# CAM_POWER.net
KiCad netlist of a schematic drawn in Altium Designer
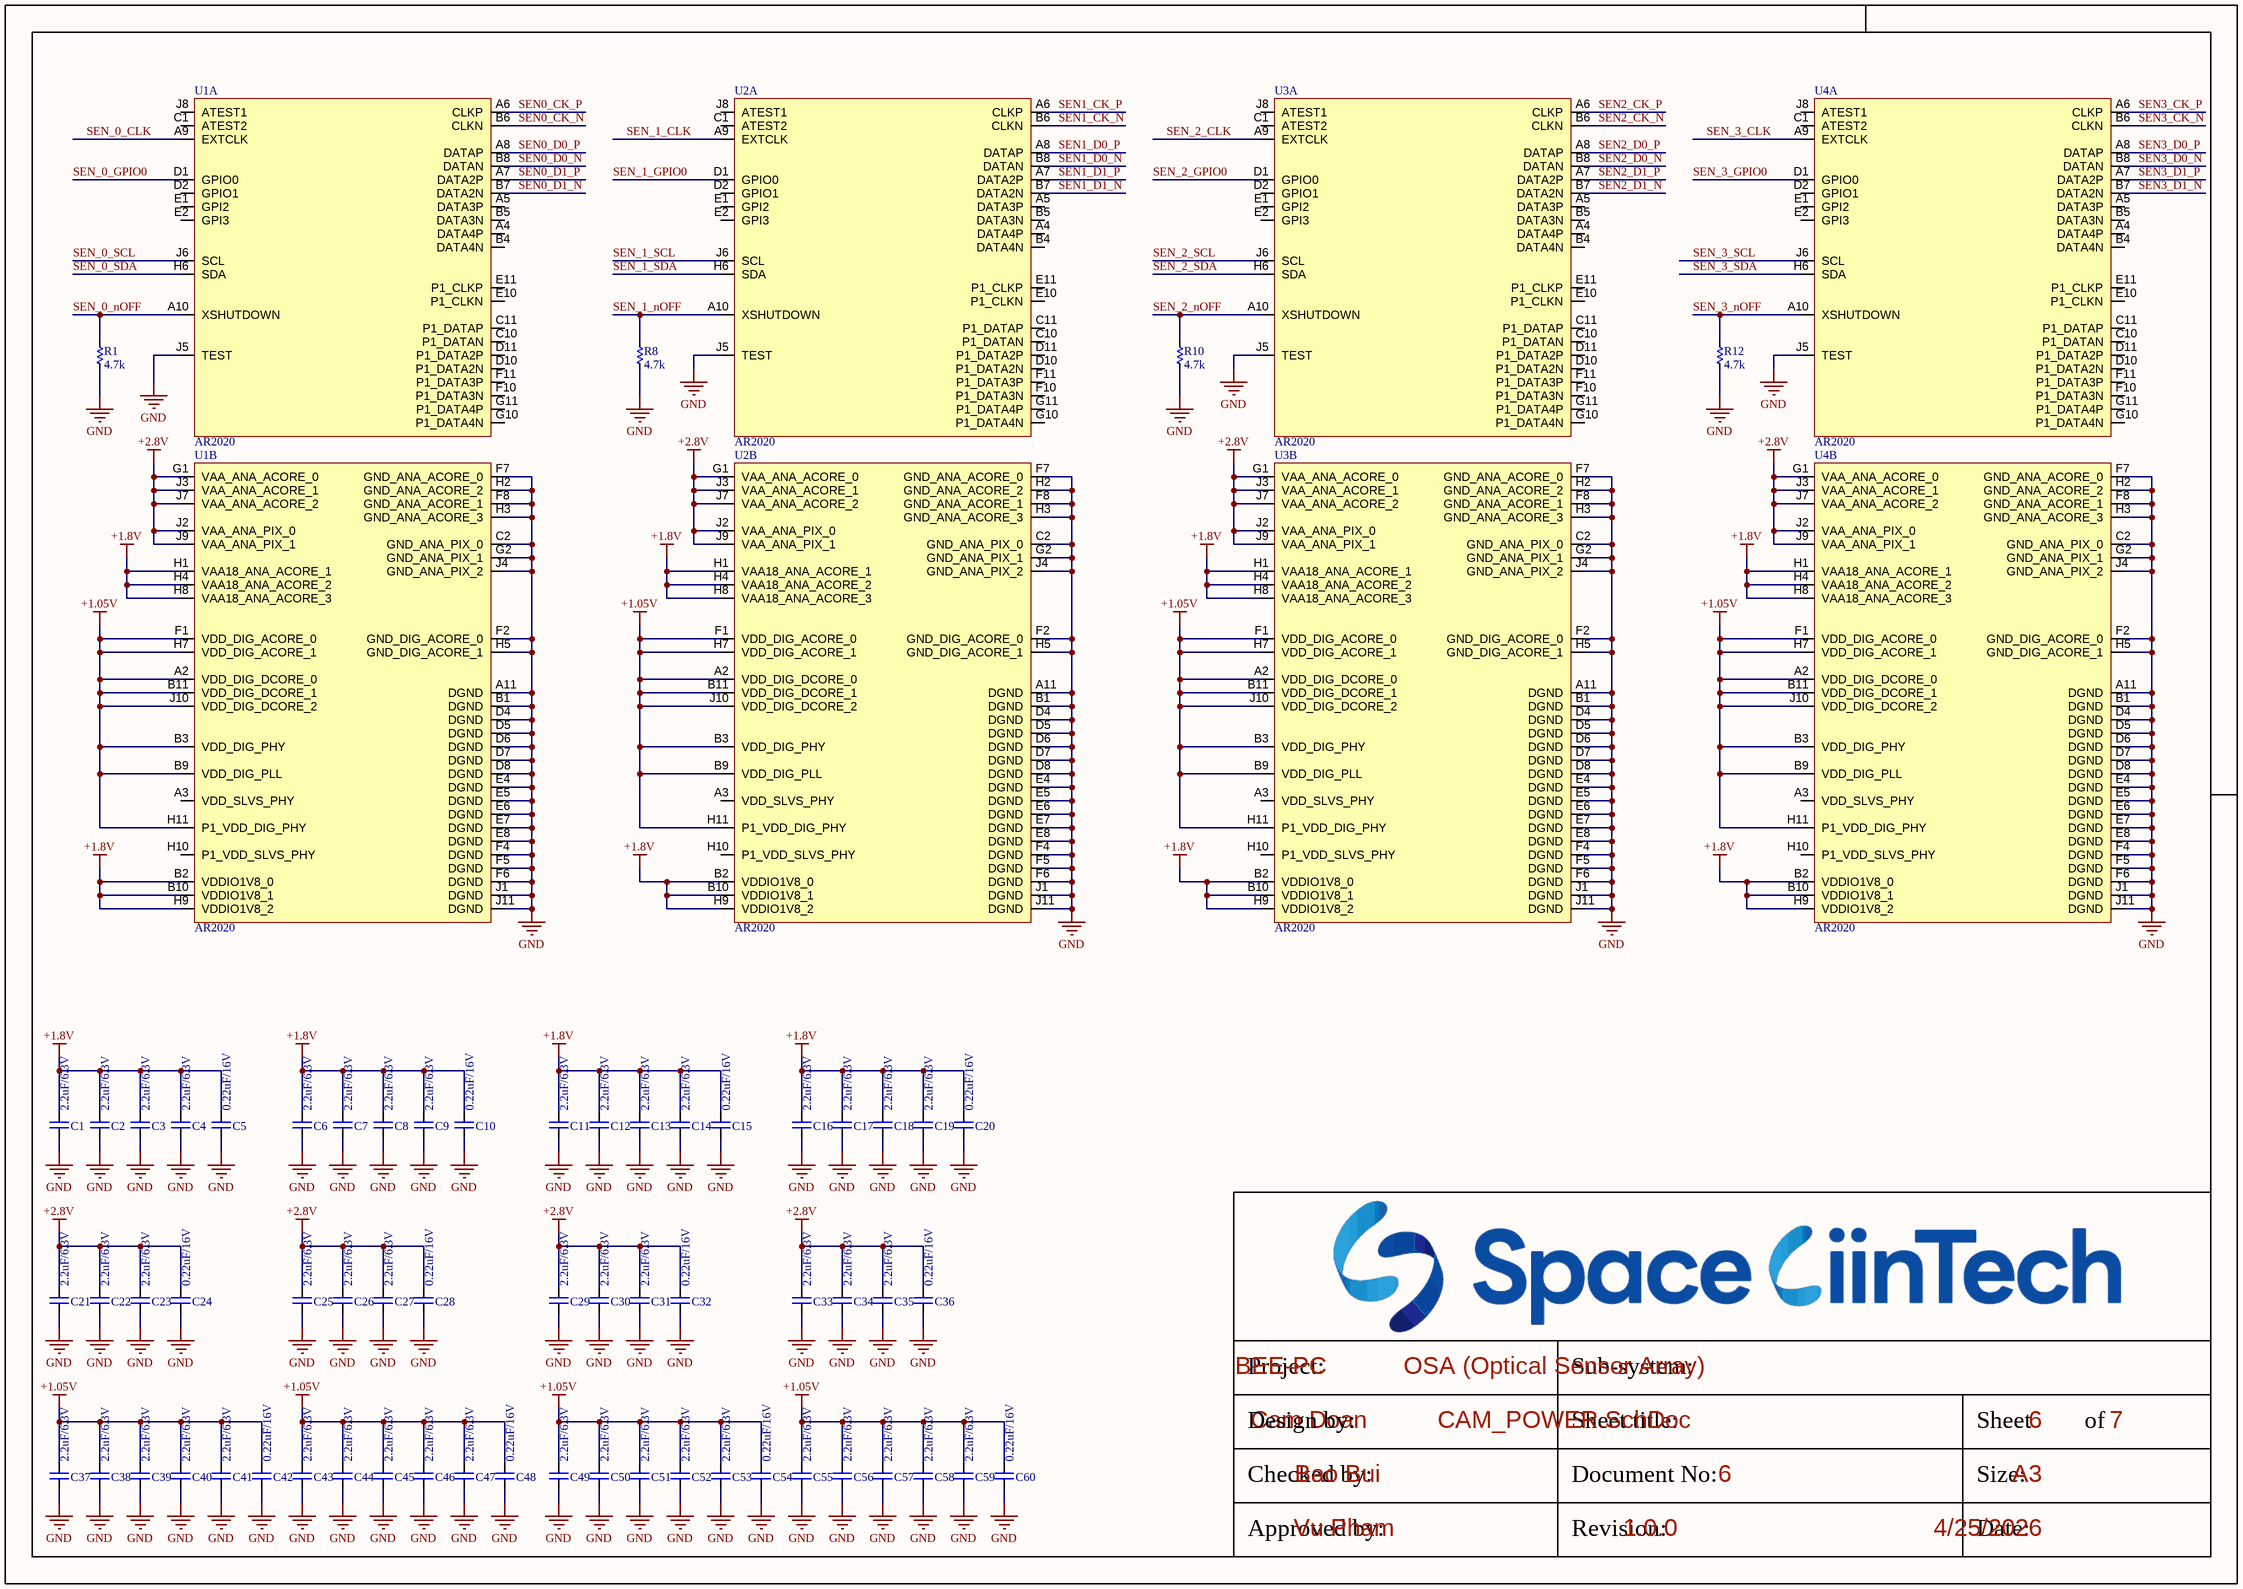
[diagram p0: CAM_POWER.SchDoc]

(export (version "E")
  (design (tool "Eeschema 10.0.6"))
  (components
    (comp (ref "C1")
      (value "2.2uF/6.3V")
      (footprint "CAP_C_1005X60")
      (description "CAP_Chip")
      (libsource (lib "LABLIB") (part "CAP_SMD"))
    )
    (comp (ref "C2")
      (value "2.2uF/6.3V")
      (footprint "CAP_C_1005X60")
      (description "CAP_Chip")
      (libsource (lib "LABLIB") (part "CAP_SMD"))
    )
    (comp (ref "C3")
      (value "2.2uF/6.3V")
      (footprint "CAP_C_1005X60")
      (description "CAP_Chip")
      (libsource (lib "LABLIB") (part "CAP_SMD"))
    )
    (comp (ref "C4")
      (value "2.2uF/6.3V")
      (footprint "CAP_C_1005X60")
      (description "CAP_Chip")
      (libsource (lib "LABLIB") (part "CAP_SMD"))
    )
    (comp (ref "C5")
      (value "0.22uF/16V")
      (footprint "CAP_C_1005X60")
      (description "CAP_Chip")
      (libsource (lib "LABLIB") (part "CAP_SMD"))
    )
    (comp (ref "C6")
      (value "2.2uF/6.3V")
      (footprint "CAP_C_1005X60")
      (description "CAP_Chip")
      (libsource (lib "LABLIB") (part "CAP_SMD"))
    )
    (comp (ref "C7")
      (value "2.2uF/6.3V")
      (footprint "CAP_C_1005X60")
      (description "CAP_Chip")
      (libsource (lib "LABLIB") (part "CAP_SMD"))
    )
    (comp (ref "C8")
      (value "2.2uF/6.3V")
      (footprint "CAP_C_1005X60")
      (description "CAP_Chip")
      (libsource (lib "LABLIB") (part "CAP_SMD"))
    )
    (comp (ref "C9")
      (value "2.2uF/6.3V")
      (footprint "CAP_C_1005X60")
      (description "CAP_Chip")
      (libsource (lib "LABLIB") (part "CAP_SMD"))
    )
    (comp (ref "C10")
      (value "0.22uF/16V")
      (footprint "CAP_C_1005X60")
      (description "CAP_Chip")
      (libsource (lib "LABLIB") (part "CAP_SMD"))
    )
    (comp (ref "C11")
      (value "2.2uF/6.3V")
      (footprint "CAP_C_1005X60")
      (description "CAP_Chip")
      (libsource (lib "LABLIB") (part "CAP_SMD"))
    )
    (comp (ref "C12")
      (value "2.2uF/6.3V")
      (footprint "CAP_C_1005X60")
      (description "CAP_Chip")
      (libsource (lib "LABLIB") (part "CAP_SMD"))
    )
    (comp (ref "C13")
      (value "2.2uF/6.3V")
      (footprint "CAP_C_1005X60")
      (description "CAP_Chip")
      (libsource (lib "LABLIB") (part "CAP_SMD"))
    )
    (comp (ref "C14")
      (value "2.2uF/6.3V")
      (footprint "CAP_C_1005X60")
      (description "CAP_Chip")
      (libsource (lib "LABLIB") (part "CAP_SMD"))
    )
    (comp (ref "C15")
      (value "0.22uF/16V")
      (footprint "CAP_C_1005X60")
      (description "CAP_Chip")
      (libsource (lib "LABLIB") (part "CAP_SMD"))
    )
    (comp (ref "C16")
      (value "2.2uF/6.3V")
      (footprint "CAP_C_1005X60")
      (description "CAP_Chip")
      (libsource (lib "LABLIB") (part "CAP_SMD"))
    )
    (comp (ref "C17")
      (value "2.2uF/6.3V")
      (footprint "CAP_C_1005X60")
      (description "CAP_Chip")
      (libsource (lib "LABLIB") (part "CAP_SMD"))
    )
    (comp (ref "C18")
      (value "2.2uF/6.3V")
      (footprint "CAP_C_1005X60")
      (description "CAP_Chip")
      (libsource (lib "LABLIB") (part "CAP_SMD"))
    )
    (comp (ref "C19")
      (value "2.2uF/6.3V")
      (footprint "CAP_C_1005X60")
      (description "CAP_Chip")
      (libsource (lib "LABLIB") (part "CAP_SMD"))
    )
    (comp (ref "C20")
      (value "0.22uF/16V")
      (footprint "CAP_C_1005X60")
      (description "CAP_Chip")
      (libsource (lib "LABLIB") (part "CAP_SMD"))
    )
    (comp (ref "C21")
      (value "2.2uF/6.3V")
      (footprint "CAP_C_1005X60")
      (description "CAP_Chip")
      (libsource (lib "LABLIB") (part "CAP_SMD"))
    )
    (comp (ref "C22")
      (value "2.2uF/6.3V")
      (footprint "CAP_C_1005X60")
      (description "CAP_Chip")
      (libsource (lib "LABLIB") (part "CAP_SMD"))
    )
    (comp (ref "C23")
      (value "2.2uF/6.3V")
      (footprint "CAP_C_1005X60")
      (description "CAP_Chip")
      (libsource (lib "LABLIB") (part "CAP_SMD"))
    )
    (comp (ref "C24")
      (value "0.22uF/16V")
      (footprint "CAP_C_1005X60")
      (description "CAP_Chip")
      (libsource (lib "LABLIB") (part "CAP_SMD"))
    )
    (comp (ref "C25")
      (value "2.2uF/6.3V")
      (footprint "CAP_C_1005X60")
      (description "CAP_Chip")
      (libsource (lib "LABLIB") (part "CAP_SMD"))
    )
    (comp (ref "C26")
      (value "2.2uF/6.3V")
      (footprint "CAP_C_1005X60")
      (description "CAP_Chip")
      (libsource (lib "LABLIB") (part "CAP_SMD"))
    )
    (comp (ref "C27")
      (value "2.2uF/6.3V")
      (footprint "CAP_C_1005X60")
      (description "CAP_Chip")
      (libsource (lib "LABLIB") (part "CAP_SMD"))
    )
    (comp (ref "C28")
      (value "0.22uF/16V")
      (footprint "CAP_C_1005X60")
      (description "CAP_Chip")
      (libsource (lib "LABLIB") (part "CAP_SMD"))
    )
    (comp (ref "C29")
      (value "2.2uF/6.3V")
      (footprint "CAP_C_1005X60")
      (description "CAP_Chip")
      (libsource (lib "LABLIB") (part "CAP_SMD"))
    )
    (comp (ref "C30")
      (value "2.2uF/6.3V")
      (footprint "CAP_C_1005X60")
      (description "CAP_Chip")
      (libsource (lib "LABLIB") (part "CAP_SMD"))
    )
    (comp (ref "C31")
      (value "2.2uF/6.3V")
      (footprint "CAP_C_1005X60")
      (description "CAP_Chip")
      (libsource (lib "LABLIB") (part "CAP_SMD"))
    )
    (comp (ref "C32")
      (value "0.22uF/16V")
      (footprint "CAP_C_1005X60")
      (description "CAP_Chip")
      (libsource (lib "LABLIB") (part "CAP_SMD"))
    )
    (comp (ref "C33")
      (value "2.2uF/6.3V")
      (footprint "CAP_C_1005X60")
      (description "CAP_Chip")
      (libsource (lib "LABLIB") (part "CAP_SMD"))
    )
    (comp (ref "C34")
      (value "2.2uF/6.3V")
      (footprint "CAP_C_1005X60")
      (description "CAP_Chip")
      (libsource (lib "LABLIB") (part "CAP_SMD"))
    )
    (comp (ref "C35")
      (value "2.2uF/6.3V")
      (footprint "CAP_C_1005X60")
      (description "CAP_Chip")
      (libsource (lib "LABLIB") (part "CAP_SMD"))
    )
    (comp (ref "C36")
      (value "0.22uF/16V")
      (footprint "CAP_C_1005X60")
      (description "CAP_Chip")
      (libsource (lib "LABLIB") (part "CAP_SMD"))
    )
    (comp (ref "C37")
      (value "2.2uF/6.3V")
      (footprint "CAP_C_1005X60")
      (description "CAP_Chip")
      (libsource (lib "LABLIB") (part "CAP_SMD"))
    )
    (comp (ref "C38")
      (value "2.2uF/6.3V")
      (footprint "CAP_C_1005X60")
      (description "CAP_Chip")
      (libsource (lib "LABLIB") (part "CAP_SMD"))
    )
    (comp (ref "C39")
      (value "2.2uF/6.3V")
      (footprint "CAP_C_1005X60")
      (description "CAP_Chip")
      (libsource (lib "LABLIB") (part "CAP_SMD"))
    )
    (comp (ref "C40")
      (value "2.2uF/6.3V")
      (footprint "CAP_C_1005X60")
      (description "CAP_Chip")
      (libsource (lib "LABLIB") (part "CAP_SMD"))
    )
    (comp (ref "C41")
      (value "2.2uF/6.3V")
      (footprint "CAP_C_1005X60")
      (description "CAP_Chip")
      (libsource (lib "LABLIB") (part "CAP_SMD"))
    )
    (comp (ref "C42")
      (value "0.22uF/16V")
      (footprint "CAP_C_1005X60")
      (description "CAP_Chip")
      (libsource (lib "LABLIB") (part "CAP_SMD"))
    )
    (comp (ref "C43")
      (value "2.2uF/6.3V")
      (footprint "CAP_C_1005X60")
      (description "CAP_Chip")
      (libsource (lib "LABLIB") (part "CAP_SMD"))
    )
    (comp (ref "C44")
      (value "2.2uF/6.3V")
      (footprint "CAP_C_1005X60")
      (description "CAP_Chip")
      (libsource (lib "LABLIB") (part "CAP_SMD"))
    )
    (comp (ref "C45")
      (value "2.2uF/6.3V")
      (footprint "CAP_C_1005X60")
      (description "CAP_Chip")
      (libsource (lib "LABLIB") (part "CAP_SMD"))
    )
    (comp (ref "C46")
      (value "2.2uF/6.3V")
      (footprint "CAP_C_1005X60")
      (description "CAP_Chip")
      (libsource (lib "LABLIB") (part "CAP_SMD"))
    )
    (comp (ref "C47")
      (value "2.2uF/6.3V")
      (footprint "CAP_C_1005X60")
      (description "CAP_Chip")
      (libsource (lib "LABLIB") (part "CAP_SMD"))
    )
    (comp (ref "C48")
      (value "0.22uF/16V")
      (footprint "CAP_C_1005X60")
      (description "CAP_Chip")
      (libsource (lib "LABLIB") (part "CAP_SMD"))
    )
    (comp (ref "C49")
      (value "2.2uF/6.3V")
      (footprint "CAP_C_1005X60")
      (description "CAP_Chip")
      (libsource (lib "LABLIB") (part "CAP_SMD"))
    )
    (comp (ref "C50")
      (value "2.2uF/6.3V")
      (footprint "CAP_C_1005X60")
      (description "CAP_Chip")
      (libsource (lib "LABLIB") (part "CAP_SMD"))
    )
    (comp (ref "C51")
      (value "2.2uF/6.3V")
      (footprint "CAP_C_1005X60")
      (description "CAP_Chip")
      (libsource (lib "LABLIB") (part "CAP_SMD"))
    )
    (comp (ref "C52")
      (value "2.2uF/6.3V")
      (footprint "CAP_C_1005X60")
      (description "CAP_Chip")
      (libsource (lib "LABLIB") (part "CAP_SMD"))
    )
    (comp (ref "C53")
      (value "2.2uF/6.3V")
      (footprint "CAP_C_1005X60")
      (description "CAP_Chip")
      (libsource (lib "LABLIB") (part "CAP_SMD"))
    )
    (comp (ref "C54")
      (value "0.22uF/16V")
      (footprint "CAP_C_1005X60")
      (description "CAP_Chip")
      (libsource (lib "LABLIB") (part "CAP_SMD"))
    )
    (comp (ref "C55")
      (value "2.2uF/6.3V")
      (footprint "CAP_C_1005X60")
      (description "CAP_Chip")
      (libsource (lib "LABLIB") (part "CAP_SMD"))
    )
    (comp (ref "C56")
      (value "2.2uF/6.3V")
      (footprint "CAP_C_1005X60")
      (description "CAP_Chip")
      (libsource (lib "LABLIB") (part "CAP_SMD"))
    )
    (comp (ref "C57")
      (value "2.2uF/6.3V")
      (footprint "CAP_C_1005X60")
      (description "CAP_Chip")
      (libsource (lib "LABLIB") (part "CAP_SMD"))
    )
    (comp (ref "C58")
      (value "2.2uF/6.3V")
      (footprint "CAP_C_1005X60")
      (description "CAP_Chip")
      (libsource (lib "LABLIB") (part "CAP_SMD"))
    )
    (comp (ref "C59")
      (value "2.2uF/6.3V")
      (footprint "CAP_C_1005X60")
      (description "CAP_Chip")
      (libsource (lib "LABLIB") (part "CAP_SMD"))
    )
    (comp (ref "C60")
      (value "0.22uF/16V")
      (footprint "CAP_C_1005X60")
      (description "CAP_Chip")
      (libsource (lib "LABLIB") (part "CAP_SMD"))
    )
    (comp (ref "R1")
      (value "4.7k")
      (footprint "RES_C_1005X40")
      (description "RES-Chip")
      (fields
        (field (name "MANUFACTURER") "Generic Components")
        (field (name "PUBLISHER") "Altium Hobart Technology Centre")
      )
      (libsource (lib "LABLIB") (part "RES-SMD"))
    )
    (comp (ref "R8")
      (value "4.7k")
      (footprint "RES_C_1005X40")
      (description "RES-Chip")
      (fields
        (field (name "MANUFACTURER") "Generic Components")
        (field (name "PUBLISHER") "Altium Hobart Technology Centre")
      )
      (libsource (lib "LABLIB") (part "RES-SMD"))
    )
    (comp (ref "R10")
      (value "4.7k")
      (footprint "RES_C_1005X40")
      (description "RES-Chip")
      (fields
        (field (name "MANUFACTURER") "Generic Components")
        (field (name "PUBLISHER") "Altium Hobart Technology Centre")
      )
      (libsource (lib "LABLIB") (part "RES-SMD"))
    )
    (comp (ref "R12")
      (value "4.7k")
      (footprint "RES_C_1005X40")
      (description "RES-Chip")
      (fields
        (field (name "MANUFACTURER") "Generic Components")
        (field (name "PUBLISHER") "Altium Hobart Technology Centre")
      )
      (libsource (lib "LABLIB") (part "RES-SMD"))
    )
    (comp (ref "U1")
      (value "AR2020")
      (footprint "BGA78C100P11X9_1300X1050X210")
      (libsource (lib "CAMERA_SchLib") (part "AR2020"))
    )
    (comp (ref "U2")
      (value "AR2020")
      (footprint "BGA78C100P11X9_1300X1050X210")
      (libsource (lib "CAMERA_SchLib") (part "AR2020"))
    )
    (comp (ref "U3")
      (value "AR2020")
      (footprint "BGA78C100P11X9_1300X1050X210")
      (libsource (lib "CAMERA_SchLib") (part "AR2020"))
    )
    (comp (ref "U4")
      (value "AR2020")
      (footprint "BGA78C100P11X9_1300X1050X210")
      (libsource (lib "CAMERA_SchLib") (part "AR2020"))
    )
  )
  (nets
    (net (code "1") (name "+1.05V") (class "Default")
      (node (ref "C37") (pin "2") (pinfunction "2_2") (pintype "passive"))
      (node (ref "C38") (pin "2") (pinfunction "2_2") (pintype "passive"))
      (node (ref "C39") (pin "2") (pinfunction "2_2") (pintype "passive"))
      (node (ref "C40") (pin "2") (pinfunction "2_2") (pintype "passive"))
      (node (ref "C41") (pin "2") (pinfunction "2_2") (pintype "passive"))
      (node (ref "C42") (pin "2") (pinfunction "2_2") (pintype "passive"))
      (node (ref "C43") (pin "2") (pinfunction "2_2") (pintype "passive"))
      (node (ref "C44") (pin "2") (pinfunction "2_2") (pintype "passive"))
      (node (ref "C45") (pin "2") (pinfunction "2_2") (pintype "passive"))
      (node (ref "C46") (pin "2") (pinfunction "2_2") (pintype "passive"))
      (node (ref "C47") (pin "2") (pinfunction "2_2") (pintype "passive"))
      (node (ref "C48") (pin "2") (pinfunction "2_2") (pintype "passive"))
      (node (ref "C49") (pin "2") (pinfunction "2_2") (pintype "passive"))
      (node (ref "C50") (pin "2") (pinfunction "2_2") (pintype "passive"))
      (node (ref "C51") (pin "2") (pinfunction "2_2") (pintype "passive"))
      (node (ref "C52") (pin "2") (pinfunction "2_2") (pintype "passive"))
      (node (ref "C53") (pin "2") (pinfunction "2_2") (pintype "passive"))
      (node (ref "C54") (pin "2") (pinfunction "2_2") (pintype "passive"))
      (node (ref "C55") (pin "2") (pinfunction "2_2") (pintype "passive"))
      (node (ref "C56") (pin "2") (pinfunction "2_2") (pintype "passive"))
      (node (ref "C57") (pin "2") (pinfunction "2_2") (pintype "passive"))
      (node (ref "C58") (pin "2") (pinfunction "2_2") (pintype "passive"))
      (node (ref "C59") (pin "2") (pinfunction "2_2") (pintype "passive"))
      (node (ref "C60") (pin "2") (pinfunction "2_2") (pintype "passive"))
      (node (ref "U1") (pin "A2") (pinfunction "VDD_DIG_DCORE_0_A2") (pintype "passive"))
      (node (ref "U1") (pin "B11") (pinfunction "VDD_DIG_DCORE_1_B11") (pintype "passive"))
      (node (ref "U1") (pin "B3") (pinfunction "VDD_DIG_PHY_B3") (pintype "passive"))
      (node (ref "U1") (pin "B9") (pinfunction "VDD_DIG_PLL_B9") (pintype "passive"))
      (node (ref "U1") (pin "F1") (pinfunction "VDD_DIG_ACORE_0_F1") (pintype "passive"))
      (node (ref "U1") (pin "H11") (pinfunction "P1_VDD_DIG_PHY_H11") (pintype "passive"))
      (node (ref "U1") (pin "H7") (pinfunction "VDD_DIG_ACORE_1_H7") (pintype "passive"))
      (node (ref "U1") (pin "J10") (pinfunction "VDD_DIG_DCORE_2_J10") (pintype "passive"))
      (node (ref "U2") (pin "A2") (pinfunction "VDD_DIG_DCORE_0_A2") (pintype "passive"))
      (node (ref "U2") (pin "B11") (pinfunction "VDD_DIG_DCORE_1_B11") (pintype "passive"))
      (node (ref "U2") (pin "B3") (pinfunction "VDD_DIG_PHY_B3") (pintype "passive"))
      (node (ref "U2") (pin "B9") (pinfunction "VDD_DIG_PLL_B9") (pintype "passive"))
      (node (ref "U2") (pin "F1") (pinfunction "VDD_DIG_ACORE_0_F1") (pintype "passive"))
      (node (ref "U2") (pin "H11") (pinfunction "P1_VDD_DIG_PHY_H11") (pintype "passive"))
      (node (ref "U2") (pin "H7") (pinfunction "VDD_DIG_ACORE_1_H7") (pintype "passive"))
      (node (ref "U2") (pin "J10") (pinfunction "VDD_DIG_DCORE_2_J10") (pintype "passive"))
      (node (ref "U3") (pin "A2") (pinfunction "VDD_DIG_DCORE_0_A2") (pintype "passive"))
      (node (ref "U3") (pin "B11") (pinfunction "VDD_DIG_DCORE_1_B11") (pintype "passive"))
      (node (ref "U3") (pin "B3") (pinfunction "VDD_DIG_PHY_B3") (pintype "passive"))
      (node (ref "U3") (pin "B9") (pinfunction "VDD_DIG_PLL_B9") (pintype "passive"))
      (node (ref "U3") (pin "F1") (pinfunction "VDD_DIG_ACORE_0_F1") (pintype "passive"))
      (node (ref "U3") (pin "H11") (pinfunction "P1_VDD_DIG_PHY_H11") (pintype "passive"))
      (node (ref "U3") (pin "H7") (pinfunction "VDD_DIG_ACORE_1_H7") (pintype "passive"))
      (node (ref "U3") (pin "J10") (pinfunction "VDD_DIG_DCORE_2_J10") (pintype "passive"))
      (node (ref "U4") (pin "A2") (pinfunction "VDD_DIG_DCORE_0_A2") (pintype "passive"))
      (node (ref "U4") (pin "B11") (pinfunction "VDD_DIG_DCORE_1_B11") (pintype "passive"))
      (node (ref "U4") (pin "B3") (pinfunction "VDD_DIG_PHY_B3") (pintype "passive"))
      (node (ref "U4") (pin "B9") (pinfunction "VDD_DIG_PLL_B9") (pintype "passive"))
      (node (ref "U4") (pin "F1") (pinfunction "VDD_DIG_ACORE_0_F1") (pintype "passive"))
      (node (ref "U4") (pin "H11") (pinfunction "P1_VDD_DIG_PHY_H11") (pintype "passive"))
      (node (ref "U4") (pin "H7") (pinfunction "VDD_DIG_ACORE_1_H7") (pintype "passive"))
      (node (ref "U4") (pin "J10") (pinfunction "VDD_DIG_DCORE_2_J10") (pintype "passive"))
    )
    (net (code "2") (name "+1.8V") (class "Default")
      (node (ref "C1") (pin "2") (pinfunction "2_2") (pintype "passive"))
      (node (ref "C10") (pin "2") (pinfunction "2_2") (pintype "passive"))
      (node (ref "C11") (pin "2") (pinfunction "2_2") (pintype "passive"))
      (node (ref "C12") (pin "2") (pinfunction "2_2") (pintype "passive"))
      (node (ref "C13") (pin "2") (pinfunction "2_2") (pintype "passive"))
      (node (ref "C14") (pin "2") (pinfunction "2_2") (pintype "passive"))
      (node (ref "C15") (pin "2") (pinfunction "2_2") (pintype "passive"))
      (node (ref "C16") (pin "2") (pinfunction "2_2") (pintype "passive"))
      (node (ref "C17") (pin "2") (pinfunction "2_2") (pintype "passive"))
      (node (ref "C18") (pin "2") (pinfunction "2_2") (pintype "passive"))
      (node (ref "C19") (pin "2") (pinfunction "2_2") (pintype "passive"))
      (node (ref "C2") (pin "2") (pinfunction "2_2") (pintype "passive"))
      (node (ref "C20") (pin "2") (pinfunction "2_2") (pintype "passive"))
      (node (ref "C3") (pin "2") (pinfunction "2_2") (pintype "passive"))
      (node (ref "C4") (pin "2") (pinfunction "2_2") (pintype "passive"))
      (node (ref "C5") (pin "2") (pinfunction "2_2") (pintype "passive"))
      (node (ref "C6") (pin "2") (pinfunction "2_2") (pintype "passive"))
      (node (ref "C7") (pin "2") (pinfunction "2_2") (pintype "passive"))
      (node (ref "C8") (pin "2") (pinfunction "2_2") (pintype "passive"))
      (node (ref "C9") (pin "2") (pinfunction "2_2") (pintype "passive"))
      (node (ref "U1") (pin "B10") (pinfunction "VDDIO1V8_1_B10") (pintype "passive"))
      (node (ref "U1") (pin "B2") (pinfunction "VDDIO1V8_0_B2") (pintype "passive"))
      (node (ref "U1") (pin "H1") (pinfunction "VAA18_ANA_ACORE_1_H1") (pintype "passive"))
      (node (ref "U1") (pin "H4") (pinfunction "VAA18_ANA_ACORE_2_H4") (pintype "passive"))
      (node (ref "U1") (pin "H8") (pinfunction "VAA18_ANA_ACORE_3_H8") (pintype "passive"))
      (node (ref "U1") (pin "H9") (pinfunction "VDDIO1V8_2_H9") (pintype "passive"))
      (node (ref "U2") (pin "B10") (pinfunction "VDDIO1V8_1_B10") (pintype "passive"))
      (node (ref "U2") (pin "B2") (pinfunction "VDDIO1V8_0_B2") (pintype "passive"))
      (node (ref "U2") (pin "H1") (pinfunction "VAA18_ANA_ACORE_1_H1") (pintype "passive"))
      (node (ref "U2") (pin "H4") (pinfunction "VAA18_ANA_ACORE_2_H4") (pintype "passive"))
      (node (ref "U2") (pin "H8") (pinfunction "VAA18_ANA_ACORE_3_H8") (pintype "passive"))
      (node (ref "U2") (pin "H9") (pinfunction "VDDIO1V8_2_H9") (pintype "passive"))
      (node (ref "U3") (pin "B10") (pinfunction "VDDIO1V8_1_B10") (pintype "passive"))
      (node (ref "U3") (pin "B2") (pinfunction "VDDIO1V8_0_B2") (pintype "passive"))
      (node (ref "U3") (pin "H1") (pinfunction "VAA18_ANA_ACORE_1_H1") (pintype "passive"))
      (node (ref "U3") (pin "H4") (pinfunction "VAA18_ANA_ACORE_2_H4") (pintype "passive"))
      (node (ref "U3") (pin "H8") (pinfunction "VAA18_ANA_ACORE_3_H8") (pintype "passive"))
      (node (ref "U3") (pin "H9") (pinfunction "VDDIO1V8_2_H9") (pintype "passive"))
      (node (ref "U4") (pin "B10") (pinfunction "VDDIO1V8_1_B10") (pintype "passive"))
      (node (ref "U4") (pin "B2") (pinfunction "VDDIO1V8_0_B2") (pintype "passive"))
      (node (ref "U4") (pin "H1") (pinfunction "VAA18_ANA_ACORE_1_H1") (pintype "passive"))
      (node (ref "U4") (pin "H4") (pinfunction "VAA18_ANA_ACORE_2_H4") (pintype "passive"))
      (node (ref "U4") (pin "H8") (pinfunction "VAA18_ANA_ACORE_3_H8") (pintype "passive"))
      (node (ref "U4") (pin "H9") (pinfunction "VDDIO1V8_2_H9") (pintype "passive"))
    )
    (net (code "3") (name "+2.8V") (class "Default")
      (node (ref "C21") (pin "2") (pinfunction "2_2") (pintype "passive"))
      (node (ref "C22") (pin "2") (pinfunction "2_2") (pintype "passive"))
      (node (ref "C23") (pin "2") (pinfunction "2_2") (pintype "passive"))
      (node (ref "C24") (pin "2") (pinfunction "2_2") (pintype "passive"))
      (node (ref "C25") (pin "2") (pinfunction "2_2") (pintype "passive"))
      (node (ref "C26") (pin "2") (pinfunction "2_2") (pintype "passive"))
      (node (ref "C27") (pin "2") (pinfunction "2_2") (pintype "passive"))
      (node (ref "C28") (pin "2") (pinfunction "2_2") (pintype "passive"))
      (node (ref "C29") (pin "2") (pinfunction "2_2") (pintype "passive"))
      (node (ref "C30") (pin "2") (pinfunction "2_2") (pintype "passive"))
      (node (ref "C31") (pin "2") (pinfunction "2_2") (pintype "passive"))
      (node (ref "C32") (pin "2") (pinfunction "2_2") (pintype "passive"))
      (node (ref "C33") (pin "2") (pinfunction "2_2") (pintype "passive"))
      (node (ref "C34") (pin "2") (pinfunction "2_2") (pintype "passive"))
      (node (ref "C35") (pin "2") (pinfunction "2_2") (pintype "passive"))
      (node (ref "C36") (pin "2") (pinfunction "2_2") (pintype "passive"))
      (node (ref "U1") (pin "G1") (pinfunction "VAA_ANA_ACORE_0_G1") (pintype "passive"))
      (node (ref "U1") (pin "J2") (pinfunction "VAA_ANA_PIX_0_J2") (pintype "passive"))
      (node (ref "U1") (pin "J3") (pinfunction "VAA_ANA_ACORE_1_J3") (pintype "passive"))
      (node (ref "U1") (pin "J7") (pinfunction "VAA_ANA_ACORE_2_J7") (pintype "passive"))
      (node (ref "U1") (pin "J9") (pinfunction "VAA_ANA_PIX_1_J9") (pintype "passive"))
      (node (ref "U2") (pin "G1") (pinfunction "VAA_ANA_ACORE_0_G1") (pintype "passive"))
      (node (ref "U2") (pin "J2") (pinfunction "VAA_ANA_PIX_0_J2") (pintype "passive"))
      (node (ref "U2") (pin "J3") (pinfunction "VAA_ANA_ACORE_1_J3") (pintype "passive"))
      (node (ref "U2") (pin "J7") (pinfunction "VAA_ANA_ACORE_2_J7") (pintype "passive"))
      (node (ref "U2") (pin "J9") (pinfunction "VAA_ANA_PIX_1_J9") (pintype "passive"))
      (node (ref "U3") (pin "G1") (pinfunction "VAA_ANA_ACORE_0_G1") (pintype "passive"))
      (node (ref "U3") (pin "J2") (pinfunction "VAA_ANA_PIX_0_J2") (pintype "passive"))
      (node (ref "U3") (pin "J3") (pinfunction "VAA_ANA_ACORE_1_J3") (pintype "passive"))
      (node (ref "U3") (pin "J7") (pinfunction "VAA_ANA_ACORE_2_J7") (pintype "passive"))
      (node (ref "U3") (pin "J9") (pinfunction "VAA_ANA_PIX_1_J9") (pintype "passive"))
      (node (ref "U4") (pin "G1") (pinfunction "VAA_ANA_ACORE_0_G1") (pintype "passive"))
      (node (ref "U4") (pin "J2") (pinfunction "VAA_ANA_PIX_0_J2") (pintype "passive"))
      (node (ref "U4") (pin "J3") (pinfunction "VAA_ANA_ACORE_1_J3") (pintype "passive"))
      (node (ref "U4") (pin "J7") (pinfunction "VAA_ANA_ACORE_2_J7") (pintype "passive"))
      (node (ref "U4") (pin "J9") (pinfunction "VAA_ANA_PIX_1_J9") (pintype "passive"))
    )
    (net (code "4") (name "/SEN0_CK_N") (class "Default")
      (node (ref "U1") (pin "B6") (pinfunction "CLKN_B6") (pintype "passive"))
    )
    (net (code "5") (name "/SEN0_CK_P") (class "Default")
      (node (ref "U1") (pin "A6") (pinfunction "CLKP_A6") (pintype "passive"))
    )
    (net (code "6") (name "/SEN0_D0_N") (class "Default")
      (node (ref "U1") (pin "B8") (pinfunction "DATAN_B8") (pintype "passive"))
    )
    (net (code "7") (name "/SEN0_D0_P") (class "Default")
      (node (ref "U1") (pin "A8") (pinfunction "DATAP_A8") (pintype "passive"))
    )
    (net (code "8") (name "/SEN0_D1_N") (class "Default")
      (node (ref "U1") (pin "B7") (pinfunction "DATA2N_B7") (pintype "passive"))
    )
    (net (code "9") (name "/SEN0_D1_P") (class "Default")
      (node (ref "U1") (pin "A7") (pinfunction "DATA2P_A7") (pintype "passive"))
    )
    (net (code "10") (name "/SEN1_CK_N") (class "Default")
      (node (ref "U2") (pin "B6") (pinfunction "CLKN_B6") (pintype "passive"))
    )
    (net (code "11") (name "/SEN1_CK_P") (class "Default")
      (node (ref "U2") (pin "A6") (pinfunction "CLKP_A6") (pintype "passive"))
    )
    (net (code "12") (name "/SEN1_D0_N") (class "Default")
      (node (ref "U2") (pin "B8") (pinfunction "DATAN_B8") (pintype "passive"))
    )
    (net (code "13") (name "/SEN1_D0_P") (class "Default")
      (node (ref "U2") (pin "A8") (pinfunction "DATAP_A8") (pintype "passive"))
    )
    (net (code "14") (name "/SEN1_D1_N") (class "Default")
      (node (ref "U2") (pin "B7") (pinfunction "DATA2N_B7") (pintype "passive"))
    )
    (net (code "15") (name "/SEN1_D1_P") (class "Default")
      (node (ref "U2") (pin "A7") (pinfunction "DATA2P_A7") (pintype "passive"))
    )
    (net (code "16") (name "/SEN2_CK_N") (class "Default")
      (node (ref "U3") (pin "B6") (pinfunction "CLKN_B6") (pintype "passive"))
    )
    (net (code "17") (name "/SEN2_CK_P") (class "Default")
      (node (ref "U3") (pin "A6") (pinfunction "CLKP_A6") (pintype "passive"))
    )
    (net (code "18") (name "/SEN2_D0_N") (class "Default")
      (node (ref "U3") (pin "B8") (pinfunction "DATAN_B8") (pintype "passive"))
    )
    (net (code "19") (name "/SEN2_D0_P") (class "Default")
      (node (ref "U3") (pin "A8") (pinfunction "DATAP_A8") (pintype "passive"))
    )
    (net (code "20") (name "/SEN2_D1_N") (class "Default")
      (node (ref "U3") (pin "B7") (pinfunction "DATA2N_B7") (pintype "passive"))
    )
    (net (code "21") (name "/SEN2_D1_P") (class "Default")
      (node (ref "U3") (pin "A7") (pinfunction "DATA2P_A7") (pintype "passive"))
    )
    (net (code "22") (name "/SEN3_CK_N") (class "Default")
      (node (ref "U4") (pin "B6") (pinfunction "CLKN_B6") (pintype "passive"))
    )
    (net (code "23") (name "/SEN3_CK_P") (class "Default")
      (node (ref "U4") (pin "A6") (pinfunction "CLKP_A6") (pintype "passive"))
    )
    (net (code "24") (name "/SEN3_D0_N") (class "Default")
      (node (ref "U4") (pin "B8") (pinfunction "DATAN_B8") (pintype "passive"))
    )
    (net (code "25") (name "/SEN3_D0_P") (class "Default")
      (node (ref "U4") (pin "A8") (pinfunction "DATAP_A8") (pintype "passive"))
    )
    (net (code "26") (name "/SEN3_D1_N") (class "Default")
      (node (ref "U4") (pin "B7") (pinfunction "DATA2N_B7") (pintype "passive"))
    )
    (net (code "27") (name "/SEN3_D1_P") (class "Default")
      (node (ref "U4") (pin "A7") (pinfunction "DATA2P_A7") (pintype "passive"))
    )
    (net (code "28") (name "/SEN_0_CLK") (class "Default")
      (node (ref "U1") (pin "A9") (pinfunction "EXTCLK_A9") (pintype "passive"))
    )
    (net (code "29") (name "/SEN_0_GPIO0") (class "Default")
      (node (ref "U1") (pin "D1") (pinfunction "GPIO0_D1") (pintype "passive"))
    )
    (net (code "30") (name "/SEN_0_SCL") (class "Default")
      (node (ref "U1") (pin "J6") (pinfunction "SCL_J6") (pintype "passive"))
    )
    (net (code "31") (name "/SEN_0_SDA") (class "Default")
      (node (ref "U1") (pin "H6") (pinfunction "SDA_H6") (pintype "passive"))
    )
    (net (code "32") (name "/SEN_0_nOFF") (class "Default")
      (node (ref "R1") (pin "1") (pinfunction "1_1") (pintype "passive"))
      (node (ref "U1") (pin "A10") (pinfunction "XSHUTDOWN_A10") (pintype "passive"))
    )
    (net (code "33") (name "/SEN_1_CLK") (class "Default")
      (node (ref "U2") (pin "A9") (pinfunction "EXTCLK_A9") (pintype "passive"))
    )
    (net (code "34") (name "/SEN_1_GPIO0") (class "Default")
      (node (ref "U2") (pin "D1") (pinfunction "GPIO0_D1") (pintype "passive"))
    )
    (net (code "35") (name "/SEN_1_SCL") (class "Default")
      (node (ref "U2") (pin "J6") (pinfunction "SCL_J6") (pintype "passive"))
    )
    (net (code "36") (name "/SEN_1_SDA") (class "Default")
      (node (ref "U2") (pin "H6") (pinfunction "SDA_H6") (pintype "passive"))
    )
    (net (code "37") (name "/SEN_1_nOFF") (class "Default")
      (node (ref "R8") (pin "1") (pinfunction "1_1") (pintype "passive"))
      (node (ref "U2") (pin "A10") (pinfunction "XSHUTDOWN_A10") (pintype "passive"))
    )
    (net (code "38") (name "/SEN_2_CLK") (class "Default")
      (node (ref "U3") (pin "A9") (pinfunction "EXTCLK_A9") (pintype "passive"))
    )
    (net (code "39") (name "/SEN_2_GPIO0") (class "Default")
      (node (ref "U3") (pin "D1") (pinfunction "GPIO0_D1") (pintype "passive"))
    )
    (net (code "40") (name "/SEN_2_SCL") (class "Default")
      (node (ref "U3") (pin "J6") (pinfunction "SCL_J6") (pintype "passive"))
    )
    (net (code "41") (name "/SEN_2_SDA") (class "Default")
      (node (ref "U3") (pin "H6") (pinfunction "SDA_H6") (pintype "passive"))
    )
    (net (code "42") (name "/SEN_2_nOFF") (class "Default")
      (node (ref "R10") (pin "1") (pinfunction "1_1") (pintype "passive"))
      (node (ref "U3") (pin "A10") (pinfunction "XSHUTDOWN_A10") (pintype "passive"))
    )
    (net (code "43") (name "/SEN_3_CLK") (class "Default")
      (node (ref "U4") (pin "A9") (pinfunction "EXTCLK_A9") (pintype "passive"))
    )
    (net (code "44") (name "/SEN_3_GPIO0") (class "Default")
      (node (ref "U4") (pin "D1") (pinfunction "GPIO0_D1") (pintype "passive"))
    )
    (net (code "45") (name "/SEN_3_SCL") (class "Default")
      (node (ref "U4") (pin "J6") (pinfunction "SCL_J6") (pintype "passive"))
    )
    (net (code "46") (name "/SEN_3_SDA") (class "Default")
      (node (ref "U4") (pin "H6") (pinfunction "SDA_H6") (pintype "passive"))
    )
    (net (code "47") (name "/SEN_3_nOFF") (class "Default")
      (node (ref "R12") (pin "1") (pinfunction "1_1") (pintype "passive"))
      (node (ref "U4") (pin "A10") (pinfunction "XSHUTDOWN_A10") (pintype "passive"))
    )
    (net (code "48") (name "GND") (class "Default")
      (node (ref "C1") (pin "1") (pinfunction "1_1") (pintype "passive"))
      (node (ref "C10") (pin "1") (pinfunction "1_1") (pintype "passive"))
      (node (ref "C11") (pin "1") (pinfunction "1_1") (pintype "passive"))
      (node (ref "C12") (pin "1") (pinfunction "1_1") (pintype "passive"))
      (node (ref "C13") (pin "1") (pinfunction "1_1") (pintype "passive"))
      (node (ref "C14") (pin "1") (pinfunction "1_1") (pintype "passive"))
      (node (ref "C15") (pin "1") (pinfunction "1_1") (pintype "passive"))
      (node (ref "C16") (pin "1") (pinfunction "1_1") (pintype "passive"))
      (node (ref "C17") (pin "1") (pinfunction "1_1") (pintype "passive"))
      (node (ref "C18") (pin "1") (pinfunction "1_1") (pintype "passive"))
      (node (ref "C19") (pin "1") (pinfunction "1_1") (pintype "passive"))
      (node (ref "C2") (pin "1") (pinfunction "1_1") (pintype "passive"))
      (node (ref "C20") (pin "1") (pinfunction "1_1") (pintype "passive"))
      (node (ref "C21") (pin "1") (pinfunction "1_1") (pintype "passive"))
      (node (ref "C22") (pin "1") (pinfunction "1_1") (pintype "passive"))
      (node (ref "C23") (pin "1") (pinfunction "1_1") (pintype "passive"))
      (node (ref "C24") (pin "1") (pinfunction "1_1") (pintype "passive"))
      (node (ref "C25") (pin "1") (pinfunction "1_1") (pintype "passive"))
      (node (ref "C26") (pin "1") (pinfunction "1_1") (pintype "passive"))
      (node (ref "C27") (pin "1") (pinfunction "1_1") (pintype "passive"))
      (node (ref "C28") (pin "1") (pinfunction "1_1") (pintype "passive"))
      (node (ref "C29") (pin "1") (pinfunction "1_1") (pintype "passive"))
      (node (ref "C3") (pin "1") (pinfunction "1_1") (pintype "passive"))
      (node (ref "C30") (pin "1") (pinfunction "1_1") (pintype "passive"))
      (node (ref "C31") (pin "1") (pinfunction "1_1") (pintype "passive"))
      (node (ref "C32") (pin "1") (pinfunction "1_1") (pintype "passive"))
      (node (ref "C33") (pin "1") (pinfunction "1_1") (pintype "passive"))
      (node (ref "C34") (pin "1") (pinfunction "1_1") (pintype "passive"))
      (node (ref "C35") (pin "1") (pinfunction "1_1") (pintype "passive"))
      (node (ref "C36") (pin "1") (pinfunction "1_1") (pintype "passive"))
      (node (ref "C37") (pin "1") (pinfunction "1_1") (pintype "passive"))
      (node (ref "C38") (pin "1") (pinfunction "1_1") (pintype "passive"))
      (node (ref "C39") (pin "1") (pinfunction "1_1") (pintype "passive"))
      (node (ref "C4") (pin "1") (pinfunction "1_1") (pintype "passive"))
      (node (ref "C40") (pin "1") (pinfunction "1_1") (pintype "passive"))
      (node (ref "C41") (pin "1") (pinfunction "1_1") (pintype "passive"))
      (node (ref "C42") (pin "1") (pinfunction "1_1") (pintype "passive"))
      (node (ref "C43") (pin "1") (pinfunction "1_1") (pintype "passive"))
      (node (ref "C44") (pin "1") (pinfunction "1_1") (pintype "passive"))
      (node (ref "C45") (pin "1") (pinfunction "1_1") (pintype "passive"))
      (node (ref "C46") (pin "1") (pinfunction "1_1") (pintype "passive"))
      (node (ref "C47") (pin "1") (pinfunction "1_1") (pintype "passive"))
      (node (ref "C48") (pin "1") (pinfunction "1_1") (pintype "passive"))
      (node (ref "C49") (pin "1") (pinfunction "1_1") (pintype "passive"))
      (node (ref "C5") (pin "1") (pinfunction "1_1") (pintype "passive"))
      (node (ref "C50") (pin "1") (pinfunction "1_1") (pintype "passive"))
      (node (ref "C51") (pin "1") (pinfunction "1_1") (pintype "passive"))
      (node (ref "C52") (pin "1") (pinfunction "1_1") (pintype "passive"))
      (node (ref "C53") (pin "1") (pinfunction "1_1") (pintype "passive"))
      (node (ref "C54") (pin "1") (pinfunction "1_1") (pintype "passive"))
      (node (ref "C55") (pin "1") (pinfunction "1_1") (pintype "passive"))
      (node (ref "C56") (pin "1") (pinfunction "1_1") (pintype "passive"))
      (node (ref "C57") (pin "1") (pinfunction "1_1") (pintype "passive"))
      (node (ref "C58") (pin "1") (pinfunction "1_1") (pintype "passive"))
      (node (ref "C59") (pin "1") (pinfunction "1_1") (pintype "passive"))
      (node (ref "C6") (pin "1") (pinfunction "1_1") (pintype "passive"))
      (node (ref "C60") (pin "1") (pinfunction "1_1") (pintype "passive"))
      (node (ref "C7") (pin "1") (pinfunction "1_1") (pintype "passive"))
      (node (ref "C8") (pin "1") (pinfunction "1_1") (pintype "passive"))
      (node (ref "C9") (pin "1") (pinfunction "1_1") (pintype "passive"))
      (node (ref "R1") (pin "2") (pinfunction "2_2") (pintype "passive"))
      (node (ref "R10") (pin "2") (pinfunction "2_2") (pintype "passive"))
      (node (ref "R12") (pin "2") (pinfunction "2_2") (pintype "passive"))
      (node (ref "R8") (pin "2") (pinfunction "2_2") (pintype "passive"))
      (node (ref "U1") (pin "A11") (pinfunction "DGND_A11") (pintype "passive"))
      (node (ref "U1") (pin "B1") (pinfunction "DGND_B1") (pintype "passive"))
      (node (ref "U1") (pin "C2") (pinfunction "GND_ANA_PIX_0_C2") (pintype "passive"))
      (node (ref "U1") (pin "D4") (pinfunction "DGND_D4") (pintype "passive"))
      (node (ref "U1") (pin "D5") (pinfunction "DGND_D5") (pintype "passive"))
      (node (ref "U1") (pin "D6") (pinfunction "DGND_D6") (pintype "passive"))
      (node (ref "U1") (pin "D7") (pinfunction "DGND_D7") (pintype "passive"))
      (node (ref "U1") (pin "D8") (pinfunction "DGND_D8") (pintype "passive"))
      (node (ref "U1") (pin "E4") (pinfunction "DGND_E4") (pintype "passive"))
      (node (ref "U1") (pin "E5") (pinfunction "DGND_E5") (pintype "passive"))
      (node (ref "U1") (pin "E6") (pinfunction "DGND_E6") (pintype "passive"))
      (node (ref "U1") (pin "E7") (pinfunction "DGND_E7") (pintype "passive"))
      (node (ref "U1") (pin "E8") (pinfunction "DGND_E8") (pintype "passive"))
      (node (ref "U1") (pin "F2") (pinfunction "GND_DIG_ACORE_0_F2") (pintype "passive"))
      (node (ref "U1") (pin "F4") (pinfunction "DGND_F4") (pintype "passive"))
      (node (ref "U1") (pin "F5") (pinfunction "DGND_F5") (pintype "passive"))
      (node (ref "U1") (pin "F6") (pinfunction "DGND_F6") (pintype "passive"))
      (node (ref "U1") (pin "F7") (pinfunction "GND_ANA_ACORE_0_F7") (pintype "passive"))
      (node (ref "U1") (pin "F8") (pinfunction "GND_ANA_ACORE_1_F8") (pintype "passive"))
      (node (ref "U1") (pin "G2") (pinfunction "GND_ANA_PIX_1_G2") (pintype "passive"))
      (node (ref "U1") (pin "H2") (pinfunction "GND_ANA_ACORE_2_H2") (pintype "passive"))
      (node (ref "U1") (pin "H3") (pinfunction "GND_ANA_ACORE_3_H3") (pintype "passive"))
      (node (ref "U1") (pin "H5") (pinfunction "GND_DIG_ACORE_1_H5") (pintype "passive"))
      (node (ref "U1") (pin "J1") (pinfunction "DGND_J1") (pintype "passive"))
      (node (ref "U1") (pin "J11") (pinfunction "DGND_J11") (pintype "passive"))
      (node (ref "U1") (pin "J4") (pinfunction "GND_ANA_PIX_2_J4") (pintype "passive"))
      (node (ref "U1") (pin "J5") (pinfunction "TEST_J5") (pintype "passive"))
      (node (ref "U2") (pin "A11") (pinfunction "DGND_A11") (pintype "passive"))
      (node (ref "U2") (pin "B1") (pinfunction "DGND_B1") (pintype "passive"))
      (node (ref "U2") (pin "C2") (pinfunction "GND_ANA_PIX_0_C2") (pintype "passive"))
      (node (ref "U2") (pin "D4") (pinfunction "DGND_D4") (pintype "passive"))
      (node (ref "U2") (pin "D5") (pinfunction "DGND_D5") (pintype "passive"))
      (node (ref "U2") (pin "D6") (pinfunction "DGND_D6") (pintype "passive"))
      (node (ref "U2") (pin "D7") (pinfunction "DGND_D7") (pintype "passive"))
      (node (ref "U2") (pin "D8") (pinfunction "DGND_D8") (pintype "passive"))
      (node (ref "U2") (pin "E4") (pinfunction "DGND_E4") (pintype "passive"))
      (node (ref "U2") (pin "E5") (pinfunction "DGND_E5") (pintype "passive"))
      (node (ref "U2") (pin "E6") (pinfunction "DGND_E6") (pintype "passive"))
      (node (ref "U2") (pin "E7") (pinfunction "DGND_E7") (pintype "passive"))
      (node (ref "U2") (pin "E8") (pinfunction "DGND_E8") (pintype "passive"))
      (node (ref "U2") (pin "F2") (pinfunction "GND_DIG_ACORE_0_F2") (pintype "passive"))
      (node (ref "U2") (pin "F4") (pinfunction "DGND_F4") (pintype "passive"))
      (node (ref "U2") (pin "F5") (pinfunction "DGND_F5") (pintype "passive"))
      (node (ref "U2") (pin "F6") (pinfunction "DGND_F6") (pintype "passive"))
      (node (ref "U2") (pin "F7") (pinfunction "GND_ANA_ACORE_0_F7") (pintype "passive"))
      (node (ref "U2") (pin "F8") (pinfunction "GND_ANA_ACORE_1_F8") (pintype "passive"))
      (node (ref "U2") (pin "G2") (pinfunction "GND_ANA_PIX_1_G2") (pintype "passive"))
      (node (ref "U2") (pin "H2") (pinfunction "GND_ANA_ACORE_2_H2") (pintype "passive"))
      (node (ref "U2") (pin "H3") (pinfunction "GND_ANA_ACORE_3_H3") (pintype "passive"))
      (node (ref "U2") (pin "H5") (pinfunction "GND_DIG_ACORE_1_H5") (pintype "passive"))
      (node (ref "U2") (pin "J1") (pinfunction "DGND_J1") (pintype "passive"))
      (node (ref "U2") (pin "J11") (pinfunction "DGND_J11") (pintype "passive"))
      (node (ref "U2") (pin "J4") (pinfunction "GND_ANA_PIX_2_J4") (pintype "passive"))
      (node (ref "U2") (pin "J5") (pinfunction "TEST_J5") (pintype "passive"))
      (node (ref "U3") (pin "A11") (pinfunction "DGND_A11") (pintype "passive"))
      (node (ref "U3") (pin "B1") (pinfunction "DGND_B1") (pintype "passive"))
      (node (ref "U3") (pin "C2") (pinfunction "GND_ANA_PIX_0_C2") (pintype "passive"))
      (node (ref "U3") (pin "D4") (pinfunction "DGND_D4") (pintype "passive"))
      (node (ref "U3") (pin "D5") (pinfunction "DGND_D5") (pintype "passive"))
      (node (ref "U3") (pin "D6") (pinfunction "DGND_D6") (pintype "passive"))
      (node (ref "U3") (pin "D7") (pinfunction "DGND_D7") (pintype "passive"))
      (node (ref "U3") (pin "D8") (pinfunction "DGND_D8") (pintype "passive"))
      (node (ref "U3") (pin "E4") (pinfunction "DGND_E4") (pintype "passive"))
      (node (ref "U3") (pin "E5") (pinfunction "DGND_E5") (pintype "passive"))
      (node (ref "U3") (pin "E6") (pinfunction "DGND_E6") (pintype "passive"))
      (node (ref "U3") (pin "E7") (pinfunction "DGND_E7") (pintype "passive"))
      (node (ref "U3") (pin "E8") (pinfunction "DGND_E8") (pintype "passive"))
      (node (ref "U3") (pin "F2") (pinfunction "GND_DIG_ACORE_0_F2") (pintype "passive"))
      (node (ref "U3") (pin "F4") (pinfunction "DGND_F4") (pintype "passive"))
      (node (ref "U3") (pin "F5") (pinfunction "DGND_F5") (pintype "passive"))
      (node (ref "U3") (pin "F6") (pinfunction "DGND_F6") (pintype "passive"))
      (node (ref "U3") (pin "F7") (pinfunction "GND_ANA_ACORE_0_F7") (pintype "passive"))
      (node (ref "U3") (pin "F8") (pinfunction "GND_ANA_ACORE_1_F8") (pintype "passive"))
      (node (ref "U3") (pin "G2") (pinfunction "GND_ANA_PIX_1_G2") (pintype "passive"))
      (node (ref "U3") (pin "H2") (pinfunction "GND_ANA_ACORE_2_H2") (pintype "passive"))
      (node (ref "U3") (pin "H3") (pinfunction "GND_ANA_ACORE_3_H3") (pintype "passive"))
      (node (ref "U3") (pin "H5") (pinfunction "GND_DIG_ACORE_1_H5") (pintype "passive"))
      (node (ref "U3") (pin "J1") (pinfunction "DGND_J1") (pintype "passive"))
      (node (ref "U3") (pin "J11") (pinfunction "DGND_J11") (pintype "passive"))
      (node (ref "U3") (pin "J4") (pinfunction "GND_ANA_PIX_2_J4") (pintype "passive"))
      (node (ref "U3") (pin "J5") (pinfunction "TEST_J5") (pintype "passive"))
      (node (ref "U4") (pin "A11") (pinfunction "DGND_A11") (pintype "passive"))
      (node (ref "U4") (pin "B1") (pinfunction "DGND_B1") (pintype "passive"))
      (node (ref "U4") (pin "C2") (pinfunction "GND_ANA_PIX_0_C2") (pintype "passive"))
      (node (ref "U4") (pin "D4") (pinfunction "DGND_D4") (pintype "passive"))
      (node (ref "U4") (pin "D5") (pinfunction "DGND_D5") (pintype "passive"))
      (node (ref "U4") (pin "D6") (pinfunction "DGND_D6") (pintype "passive"))
      (node (ref "U4") (pin "D7") (pinfunction "DGND_D7") (pintype "passive"))
      (node (ref "U4") (pin "D8") (pinfunction "DGND_D8") (pintype "passive"))
      (node (ref "U4") (pin "E4") (pinfunction "DGND_E4") (pintype "passive"))
      (node (ref "U4") (pin "E5") (pinfunction "DGND_E5") (pintype "passive"))
      (node (ref "U4") (pin "E6") (pinfunction "DGND_E6") (pintype "passive"))
      (node (ref "U4") (pin "E7") (pinfunction "DGND_E7") (pintype "passive"))
      (node (ref "U4") (pin "E8") (pinfunction "DGND_E8") (pintype "passive"))
      (node (ref "U4") (pin "F2") (pinfunction "GND_DIG_ACORE_0_F2") (pintype "passive"))
      (node (ref "U4") (pin "F4") (pinfunction "DGND_F4") (pintype "passive"))
      (node (ref "U4") (pin "F5") (pinfunction "DGND_F5") (pintype "passive"))
      (node (ref "U4") (pin "F6") (pinfunction "DGND_F6") (pintype "passive"))
      (node (ref "U4") (pin "F7") (pinfunction "GND_ANA_ACORE_0_F7") (pintype "passive"))
      (node (ref "U4") (pin "F8") (pinfunction "GND_ANA_ACORE_1_F8") (pintype "passive"))
      (node (ref "U4") (pin "G2") (pinfunction "GND_ANA_PIX_1_G2") (pintype "passive"))
      (node (ref "U4") (pin "H2") (pinfunction "GND_ANA_ACORE_2_H2") (pintype "passive"))
      (node (ref "U4") (pin "H3") (pinfunction "GND_ANA_ACORE_3_H3") (pintype "passive"))
      (node (ref "U4") (pin "H5") (pinfunction "GND_DIG_ACORE_1_H5") (pintype "passive"))
      (node (ref "U4") (pin "J1") (pinfunction "DGND_J1") (pintype "passive"))
      (node (ref "U4") (pin "J11") (pinfunction "DGND_J11") (pintype "passive"))
      (node (ref "U4") (pin "J4") (pinfunction "GND_ANA_PIX_2_J4") (pintype "passive"))
      (node (ref "U4") (pin "J5") (pinfunction "TEST_J5") (pintype "passive"))
    )
    (net (code "49") (name "unconnected-(U1A-ATEST1-PadJ8)") (class "Default")
      (node (ref "U1") (pin "J8") (pinfunction "ATEST1_J8") (pintype "passive"))
    )
    (net (code "50") (name "unconnected-(U1A-ATEST2-PadC1)") (class "Default")
      (node (ref "U1") (pin "C1") (pinfunction "ATEST2_C1") (pintype "passive"))
    )
    (net (code "51") (name "unconnected-(U1A-DATA3N-PadB5)") (class "Default")
      (node (ref "U1") (pin "B5") (pinfunction "DATA3N_B5") (pintype "passive"))
    )
    (net (code "52") (name "unconnected-(U1A-DATA3P-PadA5)") (class "Default")
      (node (ref "U1") (pin "A5") (pinfunction "DATA3P_A5") (pintype "passive"))
    )
    (net (code "53") (name "unconnected-(U1A-DATA4N-PadB4)") (class "Default")
      (node (ref "U1") (pin "B4") (pinfunction "DATA4N_B4") (pintype "passive"))
    )
    (net (code "54") (name "unconnected-(U1A-DATA4P-PadA4)") (class "Default")
      (node (ref "U1") (pin "A4") (pinfunction "DATA4P_A4") (pintype "passive"))
    )
    (net (code "55") (name "unconnected-(U1A-GPI2-PadE1)") (class "Default")
      (node (ref "U1") (pin "E1") (pinfunction "GPI2_E1") (pintype "passive"))
    )
    (net (code "56") (name "unconnected-(U1A-GPI3-PadE2)") (class "Default")
      (node (ref "U1") (pin "E2") (pinfunction "GPI3_E2") (pintype "passive"))
    )
    (net (code "57") (name "unconnected-(U1A-GPIO1-PadD2)") (class "Default")
      (node (ref "U1") (pin "D2") (pinfunction "GPIO1_D2") (pintype "passive"))
    )
    (net (code "58") (name "unconnected-(U1A-P1_CLKN-PadE10)") (class "Default")
      (node (ref "U1") (pin "E10") (pinfunction "P1_CLKN_E10") (pintype "passive"))
    )
    (net (code "59") (name "unconnected-(U1A-P1_CLKP-PadE11)") (class "Default")
      (node (ref "U1") (pin "E11") (pinfunction "P1_CLKP_E11") (pintype "passive"))
    )
    (net (code "60") (name "unconnected-(U1A-P1_DATA2N-PadD10)") (class "Default")
      (node (ref "U1") (pin "D10") (pinfunction "P1_DATA2N_D10") (pintype "passive"))
    )
    (net (code "61") (name "unconnected-(U1A-P1_DATA2P-PadD11)") (class "Default")
      (node (ref "U1") (pin "D11") (pinfunction "P1_DATA2P_D11") (pintype "passive"))
    )
    (net (code "62") (name "unconnected-(U1A-P1_DATA3N-PadF10)") (class "Default")
      (node (ref "U1") (pin "F10") (pinfunction "P1_DATA3N_F10") (pintype "passive"))
    )
    (net (code "63") (name "unconnected-(U1A-P1_DATA3P-PadF11)") (class "Default")
      (node (ref "U1") (pin "F11") (pinfunction "P1_DATA3P_F11") (pintype "passive"))
    )
    (net (code "64") (name "unconnected-(U1A-P1_DATA4N-PadG10)") (class "Default")
      (node (ref "U1") (pin "G10") (pinfunction "P1_DATA4N_G10") (pintype "passive"))
    )
    (net (code "65") (name "unconnected-(U1A-P1_DATA4P-PadG11)") (class "Default")
      (node (ref "U1") (pin "G11") (pinfunction "P1_DATA4P_G11") (pintype "passive"))
    )
    (net (code "66") (name "unconnected-(U1A-P1_DATAN-PadC10)") (class "Default")
      (node (ref "U1") (pin "C10") (pinfunction "P1_DATAN_C10") (pintype "passive"))
    )
    (net (code "67") (name "unconnected-(U1A-P1_DATAP-PadC11)") (class "Default")
      (node (ref "U1") (pin "C11") (pinfunction "P1_DATAP_C11") (pintype "passive"))
    )
    (net (code "68") (name "unconnected-(U1B-P1_VDD_SLVS_PHY-PadH10)") (class "Default")
      (node (ref "U1") (pin "H10") (pinfunction "P1_VDD_SLVS_PHY_H10") (pintype "passive"))
    )
    (net (code "69") (name "unconnected-(U1B-VDD_SLVS_PHY-PadA3)") (class "Default")
      (node (ref "U1") (pin "A3") (pinfunction "VDD_SLVS_PHY_A3") (pintype "passive"))
    )
    (net (code "70") (name "unconnected-(U2A-ATEST1-PadJ8)") (class "Default")
      (node (ref "U2") (pin "J8") (pinfunction "ATEST1_J8") (pintype "passive"))
    )
    (net (code "71") (name "unconnected-(U2A-ATEST2-PadC1)") (class "Default")
      (node (ref "U2") (pin "C1") (pinfunction "ATEST2_C1") (pintype "passive"))
    )
    (net (code "72") (name "unconnected-(U2A-DATA3N-PadB5)") (class "Default")
      (node (ref "U2") (pin "B5") (pinfunction "DATA3N_B5") (pintype "passive"))
    )
    (net (code "73") (name "unconnected-(U2A-DATA3P-PadA5)") (class "Default")
      (node (ref "U2") (pin "A5") (pinfunction "DATA3P_A5") (pintype "passive"))
    )
    (net (code "74") (name "unconnected-(U2A-DATA4N-PadB4)") (class "Default")
      (node (ref "U2") (pin "B4") (pinfunction "DATA4N_B4") (pintype "passive"))
    )
    (net (code "75") (name "unconnected-(U2A-DATA4P-PadA4)") (class "Default")
      (node (ref "U2") (pin "A4") (pinfunction "DATA4P_A4") (pintype "passive"))
    )
    (net (code "76") (name "unconnected-(U2A-GPI2-PadE1)") (class "Default")
      (node (ref "U2") (pin "E1") (pinfunction "GPI2_E1") (pintype "passive"))
    )
    (net (code "77") (name "unconnected-(U2A-GPI3-PadE2)") (class "Default")
      (node (ref "U2") (pin "E2") (pinfunction "GPI3_E2") (pintype "passive"))
    )
    (net (code "78") (name "unconnected-(U2A-GPIO1-PadD2)") (class "Default")
      (node (ref "U2") (pin "D2") (pinfunction "GPIO1_D2") (pintype "passive"))
    )
    (net (code "79") (name "unconnected-(U2A-P1_CLKN-PadE10)") (class "Default")
      (node (ref "U2") (pin "E10") (pinfunction "P1_CLKN_E10") (pintype "passive"))
    )
    (net (code "80") (name "unconnected-(U2A-P1_CLKP-PadE11)") (class "Default")
      (node (ref "U2") (pin "E11") (pinfunction "P1_CLKP_E11") (pintype "passive"))
    )
    (net (code "81") (name "unconnected-(U2A-P1_DATA2N-PadD10)") (class "Default")
      (node (ref "U2") (pin "D10") (pinfunction "P1_DATA2N_D10") (pintype "passive"))
    )
    (net (code "82") (name "unconnected-(U2A-P1_DATA2P-PadD11)") (class "Default")
      (node (ref "U2") (pin "D11") (pinfunction "P1_DATA2P_D11") (pintype "passive"))
    )
    (net (code "83") (name "unconnected-(U2A-P1_DATA3N-PadF10)") (class "Default")
      (node (ref "U2") (pin "F10") (pinfunction "P1_DATA3N_F10") (pintype "passive"))
    )
    (net (code "84") (name "unconnected-(U2A-P1_DATA3P-PadF11)") (class "Default")
      (node (ref "U2") (pin "F11") (pinfunction "P1_DATA3P_F11") (pintype "passive"))
    )
    (net (code "85") (name "unconnected-(U2A-P1_DATA4N-PadG10)") (class "Default")
      (node (ref "U2") (pin "G10") (pinfunction "P1_DATA4N_G10") (pintype "passive"))
    )
    (net (code "86") (name "unconnected-(U2A-P1_DATA4P-PadG11)") (class "Default")
      (node (ref "U2") (pin "G11") (pinfunction "P1_DATA4P_G11") (pintype "passive"))
    )
    (net (code "87") (name "unconnected-(U2A-P1_DATAN-PadC10)") (class "Default")
      (node (ref "U2") (pin "C10") (pinfunction "P1_DATAN_C10") (pintype "passive"))
    )
    (net (code "88") (name "unconnected-(U2A-P1_DATAP-PadC11)") (class "Default")
      (node (ref "U2") (pin "C11") (pinfunction "P1_DATAP_C11") (pintype "passive"))
    )
    (net (code "89") (name "unconnected-(U2B-P1_VDD_SLVS_PHY-PadH10)") (class "Default")
      (node (ref "U2") (pin "H10") (pinfunction "P1_VDD_SLVS_PHY_H10") (pintype "passive"))
    )
    (net (code "90") (name "unconnected-(U2B-VDD_SLVS_PHY-PadA3)") (class "Default")
      (node (ref "U2") (pin "A3") (pinfunction "VDD_SLVS_PHY_A3") (pintype "passive"))
    )
    (net (code "91") (name "unconnected-(U3A-ATEST1-PadJ8)") (class "Default")
      (node (ref "U3") (pin "J8") (pinfunction "ATEST1_J8") (pintype "passive"))
    )
    (net (code "92") (name "unconnected-(U3A-ATEST2-PadC1)") (class "Default")
      (node (ref "U3") (pin "C1") (pinfunction "ATEST2_C1") (pintype "passive"))
    )
    (net (code "93") (name "unconnected-(U3A-DATA3N-PadB5)") (class "Default")
      (node (ref "U3") (pin "B5") (pinfunction "DATA3N_B5") (pintype "passive"))
    )
    (net (code "94") (name "unconnected-(U3A-DATA3P-PadA5)") (class "Default")
      (node (ref "U3") (pin "A5") (pinfunction "DATA3P_A5") (pintype "passive"))
    )
    (net (code "95") (name "unconnected-(U3A-DATA4N-PadB4)") (class "Default")
      (node (ref "U3") (pin "B4") (pinfunction "DATA4N_B4") (pintype "passive"))
    )
    (net (code "96") (name "unconnected-(U3A-DATA4P-PadA4)") (class "Default")
      (node (ref "U3") (pin "A4") (pinfunction "DATA4P_A4") (pintype "passive"))
    )
    (net (code "97") (name "unconnected-(U3A-GPI2-PadE1)") (class "Default")
      (node (ref "U3") (pin "E1") (pinfunction "GPI2_E1") (pintype "passive"))
    )
    (net (code "98") (name "unconnected-(U3A-GPI3-PadE2)") (class "Default")
      (node (ref "U3") (pin "E2") (pinfunction "GPI3_E2") (pintype "passive"))
    )
    (net (code "99") (name "unconnected-(U3A-GPIO1-PadD2)") (class "Default")
      (node (ref "U3") (pin "D2") (pinfunction "GPIO1_D2") (pintype "passive"))
    )
    (net (code "100") (name "unconnected-(U3A-P1_CLKN-PadE10)") (class "Default")
      (node (ref "U3") (pin "E10") (pinfunction "P1_CLKN_E10") (pintype "passive"))
    )
    (net (code "101") (name "unconnected-(U3A-P1_CLKP-PadE11)") (class "Default")
      (node (ref "U3") (pin "E11") (pinfunction "P1_CLKP_E11") (pintype "passive"))
    )
    (net (code "102") (name "unconnected-(U3A-P1_DATA2N-PadD10)") (class "Default")
      (node (ref "U3") (pin "D10") (pinfunction "P1_DATA2N_D10") (pintype "passive"))
    )
    (net (code "103") (name "unconnected-(U3A-P1_DATA2P-PadD11)") (class "Default")
      (node (ref "U3") (pin "D11") (pinfunction "P1_DATA2P_D11") (pintype "passive"))
    )
    (net (code "104") (name "unconnected-(U3A-P1_DATA3N-PadF10)") (class "Default")
      (node (ref "U3") (pin "F10") (pinfunction "P1_DATA3N_F10") (pintype "passive"))
    )
    (net (code "105") (name "unconnected-(U3A-P1_DATA3P-PadF11)") (class "Default")
      (node (ref "U3") (pin "F11") (pinfunction "P1_DATA3P_F11") (pintype "passive"))
    )
    (net (code "106") (name "unconnected-(U3A-P1_DATA4N-PadG10)") (class "Default")
      (node (ref "U3") (pin "G10") (pinfunction "P1_DATA4N_G10") (pintype "passive"))
    )
    (net (code "107") (name "unconnected-(U3A-P1_DATA4P-PadG11)") (class "Default")
      (node (ref "U3") (pin "G11") (pinfunction "P1_DATA4P_G11") (pintype "passive"))
    )
    (net (code "108") (name "unconnected-(U3A-P1_DATAN-PadC10)") (class "Default")
      (node (ref "U3") (pin "C10") (pinfunction "P1_DATAN_C10") (pintype "passive"))
    )
    (net (code "109") (name "unconnected-(U3A-P1_DATAP-PadC11)") (class "Default")
      (node (ref "U3") (pin "C11") (pinfunction "P1_DATAP_C11") (pintype "passive"))
    )
    (net (code "110") (name "unconnected-(U3B-P1_VDD_SLVS_PHY-PadH10)") (class "Default")
      (node (ref "U3") (pin "H10") (pinfunction "P1_VDD_SLVS_PHY_H10") (pintype "passive"))
    )
    (net (code "111") (name "unconnected-(U3B-VDD_SLVS_PHY-PadA3)") (class "Default")
      (node (ref "U3") (pin "A3") (pinfunction "VDD_SLVS_PHY_A3") (pintype "passive"))
    )
    (net (code "112") (name "unconnected-(U4A-ATEST1-PadJ8)") (class "Default")
      (node (ref "U4") (pin "J8") (pinfunction "ATEST1_J8") (pintype "passive"))
    )
    (net (code "113") (name "unconnected-(U4A-ATEST2-PadC1)") (class "Default")
      (node (ref "U4") (pin "C1") (pinfunction "ATEST2_C1") (pintype "passive"))
    )
    (net (code "114") (name "unconnected-(U4A-DATA3N-PadB5)") (class "Default")
      (node (ref "U4") (pin "B5") (pinfunction "DATA3N_B5") (pintype "passive"))
    )
    (net (code "115") (name "unconnected-(U4A-DATA3P-PadA5)") (class "Default")
      (node (ref "U4") (pin "A5") (pinfunction "DATA3P_A5") (pintype "passive"))
    )
    (net (code "116") (name "unconnected-(U4A-DATA4N-PadB4)") (class "Default")
      (node (ref "U4") (pin "B4") (pinfunction "DATA4N_B4") (pintype "passive"))
    )
    (net (code "117") (name "unconnected-(U4A-DATA4P-PadA4)") (class "Default")
      (node (ref "U4") (pin "A4") (pinfunction "DATA4P_A4") (pintype "passive"))
    )
    (net (code "118") (name "unconnected-(U4A-GPI2-PadE1)") (class "Default")
      (node (ref "U4") (pin "E1") (pinfunction "GPI2_E1") (pintype "passive"))
    )
    (net (code "119") (name "unconnected-(U4A-GPI3-PadE2)") (class "Default")
      (node (ref "U4") (pin "E2") (pinfunction "GPI3_E2") (pintype "passive"))
    )
    (net (code "120") (name "unconnected-(U4A-GPIO1-PadD2)") (class "Default")
      (node (ref "U4") (pin "D2") (pinfunction "GPIO1_D2") (pintype "passive"))
    )
    (net (code "121") (name "unconnected-(U4A-P1_CLKN-PadE10)") (class "Default")
      (node (ref "U4") (pin "E10") (pinfunction "P1_CLKN_E10") (pintype "passive"))
    )
    (net (code "122") (name "unconnected-(U4A-P1_CLKP-PadE11)") (class "Default")
      (node (ref "U4") (pin "E11") (pinfunction "P1_CLKP_E11") (pintype "passive"))
    )
    (net (code "123") (name "unconnected-(U4A-P1_DATA2N-PadD10)") (class "Default")
      (node (ref "U4") (pin "D10") (pinfunction "P1_DATA2N_D10") (pintype "passive"))
    )
    (net (code "124") (name "unconnected-(U4A-P1_DATA2P-PadD11)") (class "Default")
      (node (ref "U4") (pin "D11") (pinfunction "P1_DATA2P_D11") (pintype "passive"))
    )
    (net (code "125") (name "unconnected-(U4A-P1_DATA3N-PadF10)") (class "Default")
      (node (ref "U4") (pin "F10") (pinfunction "P1_DATA3N_F10") (pintype "passive"))
    )
    (net (code "126") (name "unconnected-(U4A-P1_DATA3P-PadF11)") (class "Default")
      (node (ref "U4") (pin "F11") (pinfunction "P1_DATA3P_F11") (pintype "passive"))
    )
    (net (code "127") (name "unconnected-(U4A-P1_DATA4N-PadG10)") (class "Default")
      (node (ref "U4") (pin "G10") (pinfunction "P1_DATA4N_G10") (pintype "passive"))
    )
    (net (code "128") (name "unconnected-(U4A-P1_DATA4P-PadG11)") (class "Default")
      (node (ref "U4") (pin "G11") (pinfunction "P1_DATA4P_G11") (pintype "passive"))
    )
    (net (code "129") (name "unconnected-(U4A-P1_DATAN-PadC10)") (class "Default")
      (node (ref "U4") (pin "C10") (pinfunction "P1_DATAN_C10") (pintype "passive"))
    )
    (net (code "130") (name "unconnected-(U4A-P1_DATAP-PadC11)") (class "Default")
      (node (ref "U4") (pin "C11") (pinfunction "P1_DATAP_C11") (pintype "passive"))
    )
    (net (code "131") (name "unconnected-(U4B-P1_VDD_SLVS_PHY-PadH10)") (class "Default")
      (node (ref "U4") (pin "H10") (pinfunction "P1_VDD_SLVS_PHY_H10") (pintype "passive"))
    )
    (net (code "132") (name "unconnected-(U4B-VDD_SLVS_PHY-PadA3)") (class "Default")
      (node (ref "U4") (pin "A3") (pinfunction "VDD_SLVS_PHY_A3") (pintype "passive"))
    )
  )
)
